# cistercianDisplay.net
KiCad netlist of a schematic drawn in EAGLE
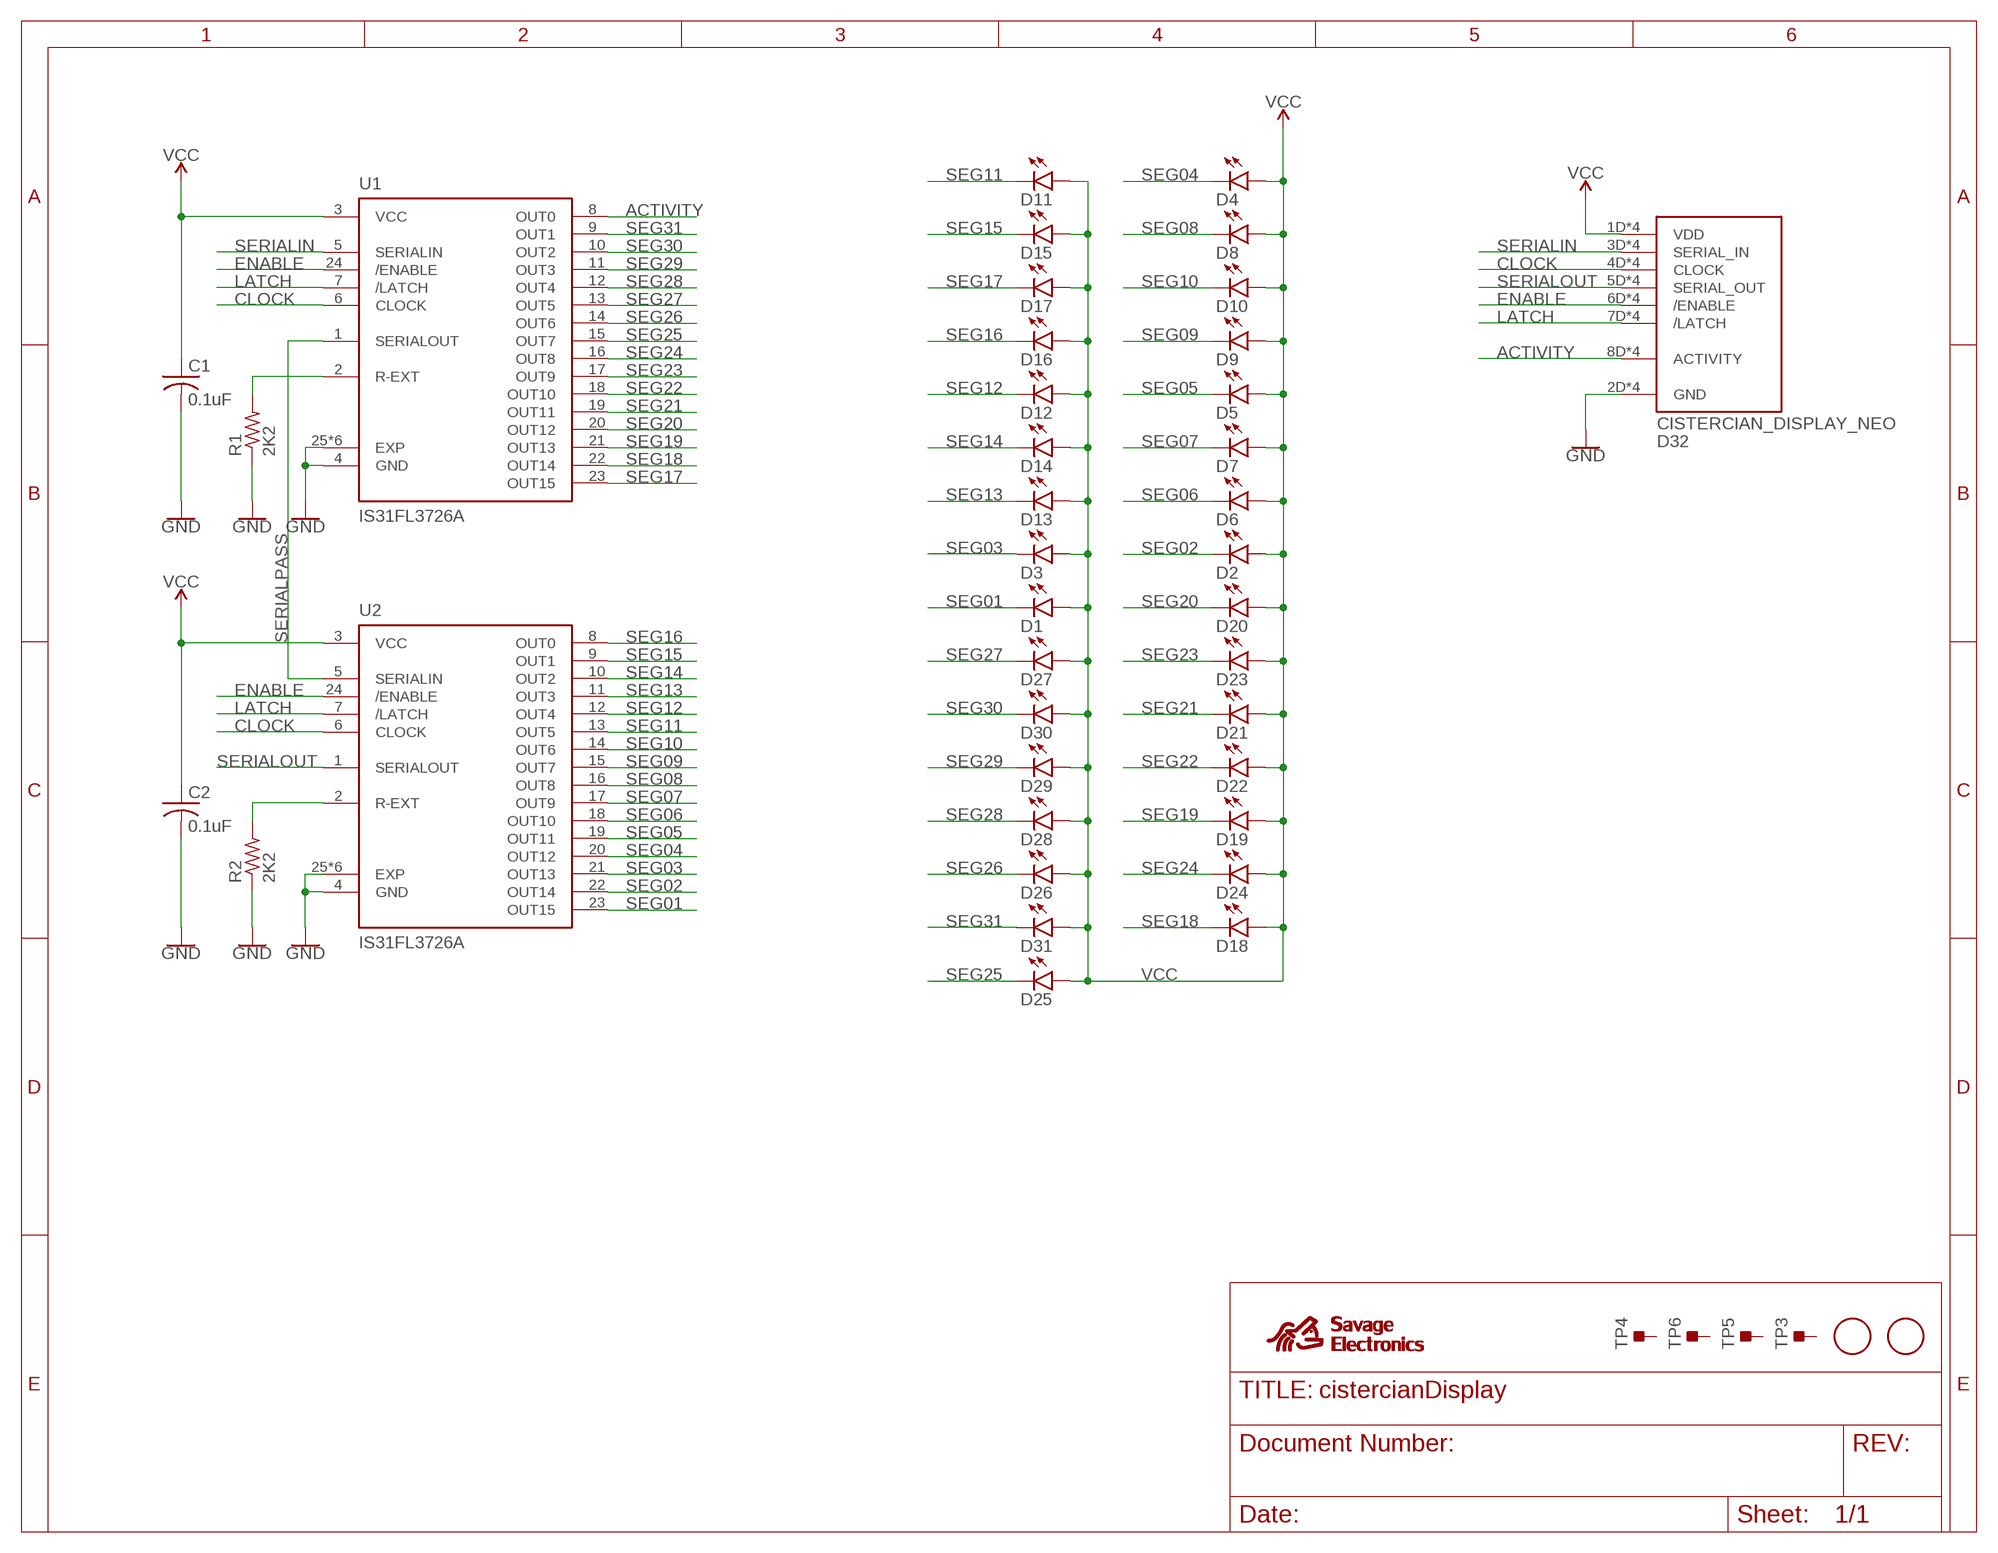
[diagram p0: schematic, sheet 1]

(export (version "E")
  (design (tool "Eeschema 10.0.6"))
  (components
    (comp (ref "C1")
      (value "0.1uF")
      (footprint "eagle-import:C0603")
      (libsource (lib "eagle-import") (part "C-USC0603"))
    )
    (comp (ref "C2")
      (value "0.1uF")
      (footprint "eagle-import:C0603")
      (libsource (lib "eagle-import") (part "C-USC0603"))
    )
    (comp (ref "D1")
      (value "LEDCHIP-LED0805")
      (footprint "eagle-import:CHIP-LED0805")
      (libsource (lib "eagle-import") (part "LEDCHIP-LED0805"))
    )
    (comp (ref "D2")
      (value "LEDCHIP-LED0805")
      (footprint "eagle-import:CHIP-LED0805")
      (libsource (lib "eagle-import") (part "LEDCHIP-LED0805"))
    )
    (comp (ref "D3")
      (value "LEDCHIP-LED0805")
      (footprint "eagle-import:CHIP-LED0805")
      (libsource (lib "eagle-import") (part "LEDCHIP-LED0805"))
    )
    (comp (ref "D4")
      (value "LEDCHIP-LED0805")
      (footprint "eagle-import:CHIP-LED0805")
      (libsource (lib "eagle-import") (part "LEDCHIP-LED0805"))
    )
    (comp (ref "D5")
      (value "LEDCHIP-LED0805")
      (footprint "eagle-import:CHIP-LED0805")
      (libsource (lib "eagle-import") (part "LEDCHIP-LED0805"))
    )
    (comp (ref "D6")
      (value "LEDCHIP-LED0805")
      (footprint "eagle-import:CHIP-LED0805")
      (libsource (lib "eagle-import") (part "LEDCHIP-LED0805"))
    )
    (comp (ref "D7")
      (value "LEDCHIP-LED0805")
      (footprint "eagle-import:CHIP-LED0805")
      (libsource (lib "eagle-import") (part "LEDCHIP-LED0805"))
    )
    (comp (ref "D8")
      (value "LEDCHIP-LED0805")
      (footprint "eagle-import:CHIP-LED0805")
      (libsource (lib "eagle-import") (part "LEDCHIP-LED0805"))
    )
    (comp (ref "D9")
      (value "LEDCHIP-LED0805")
      (footprint "eagle-import:CHIP-LED0805")
      (libsource (lib "eagle-import") (part "LEDCHIP-LED0805"))
    )
    (comp (ref "D10")
      (value "LEDCHIP-LED0805")
      (footprint "eagle-import:CHIP-LED0805")
      (libsource (lib "eagle-import") (part "LEDCHIP-LED0805"))
    )
    (comp (ref "D11")
      (value "LEDCHIP-LED0805")
      (footprint "eagle-import:CHIP-LED0805")
      (libsource (lib "eagle-import") (part "LEDCHIP-LED0805"))
    )
    (comp (ref "D12")
      (value "LEDCHIP-LED0805")
      (footprint "eagle-import:CHIP-LED0805")
      (libsource (lib "eagle-import") (part "LEDCHIP-LED0805"))
    )
    (comp (ref "D13")
      (value "LEDCHIP-LED0805")
      (footprint "eagle-import:CHIP-LED0805")
      (libsource (lib "eagle-import") (part "LEDCHIP-LED0805"))
    )
    (comp (ref "D14")
      (value "LEDCHIP-LED0805")
      (footprint "eagle-import:CHIP-LED0805")
      (libsource (lib "eagle-import") (part "LEDCHIP-LED0805"))
    )
    (comp (ref "D15")
      (value "LEDCHIP-LED0805")
      (footprint "eagle-import:CHIP-LED0805")
      (libsource (lib "eagle-import") (part "LEDCHIP-LED0805"))
    )
    (comp (ref "D16")
      (value "LEDCHIP-LED0805")
      (footprint "eagle-import:CHIP-LED0805")
      (libsource (lib "eagle-import") (part "LEDCHIP-LED0805"))
    )
    (comp (ref "D17")
      (value "LEDCHIP-LED0805")
      (footprint "eagle-import:CHIP-LED0805")
      (libsource (lib "eagle-import") (part "LEDCHIP-LED0805"))
    )
    (comp (ref "D18")
      (value "LEDCHIP-LED0805")
      (footprint "eagle-import:CHIP-LED0805")
      (libsource (lib "eagle-import") (part "LEDCHIP-LED0805"))
    )
    (comp (ref "D19")
      (value "LEDCHIP-LED0805")
      (footprint "eagle-import:CHIP-LED0805")
      (libsource (lib "eagle-import") (part "LEDCHIP-LED0805"))
    )
    (comp (ref "D20")
      (value "LEDCHIP-LED0805")
      (footprint "eagle-import:CHIP-LED0805")
      (libsource (lib "eagle-import") (part "LEDCHIP-LED0805"))
    )
    (comp (ref "D21")
      (value "LEDCHIP-LED0805")
      (footprint "eagle-import:CHIP-LED0805")
      (libsource (lib "eagle-import") (part "LEDCHIP-LED0805"))
    )
    (comp (ref "D22")
      (value "LEDCHIP-LED0805")
      (footprint "eagle-import:CHIP-LED0805")
      (libsource (lib "eagle-import") (part "LEDCHIP-LED0805"))
    )
    (comp (ref "D23")
      (value "LEDCHIP-LED0805")
      (footprint "eagle-import:CHIP-LED0805")
      (libsource (lib "eagle-import") (part "LEDCHIP-LED0805"))
    )
    (comp (ref "D24")
      (value "LEDCHIP-LED0805")
      (footprint "eagle-import:CHIP-LED0805")
      (libsource (lib "eagle-import") (part "LEDCHIP-LED0805"))
    )
    (comp (ref "D25")
      (value "LEDCHIP-LED0805")
      (footprint "eagle-import:CHIP-LED0805")
      (libsource (lib "eagle-import") (part "LEDCHIP-LED0805"))
    )
    (comp (ref "D26")
      (value "LEDCHIP-LED0805")
      (footprint "eagle-import:CHIP-LED0805")
      (libsource (lib "eagle-import") (part "LEDCHIP-LED0805"))
    )
    (comp (ref "D27")
      (value "LEDCHIP-LED0805")
      (footprint "eagle-import:CHIP-LED0805")
      (libsource (lib "eagle-import") (part "LEDCHIP-LED0805"))
    )
    (comp (ref "D28")
      (value "LEDCHIP-LED0805")
      (footprint "eagle-import:CHIP-LED0805")
      (libsource (lib "eagle-import") (part "LEDCHIP-LED0805"))
    )
    (comp (ref "D29")
      (value "LEDCHIP-LED0805")
      (footprint "eagle-import:CHIP-LED0805")
      (libsource (lib "eagle-import") (part "LEDCHIP-LED0805"))
    )
    (comp (ref "D30")
      (value "LEDCHIP-LED0805")
      (footprint "eagle-import:CHIP-LED0805")
      (libsource (lib "eagle-import") (part "LEDCHIP-LED0805"))
    )
    (comp (ref "D31")
      (value "LEDCHIP-LED0805")
      (footprint "eagle-import:CHIP-LED0805")
      (libsource (lib "eagle-import") (part "LEDCHIP-LED0805"))
    )
    (comp (ref "D32")
      (value "CISTERCIAN_DISPLAY_NEO")
      (footprint "eagle-import:CISTERCIAN_DISPLAYNEO")
      (libsource (lib "eagle-import") (part "CISTERCIAN_DISPLAY_NEO"))
    )
    (comp (ref "R1")
      (value "2K2")
      (footprint "eagle-import:R0603")
      (libsource (lib "eagle-import") (part "R-US_R0603"))
    )
    (comp (ref "R2")
      (value "2K2")
      (footprint "eagle-import:R0603")
      (libsource (lib "eagle-import") (part "R-US_R0603"))
    )
    (comp (ref "TP3")
      (value "TESTPOINT_TPS-SMD-10SN")
      (footprint "eagle-import:TESTPOINT_SMD-10SN")
      (libsource (lib "eagle-import") (part "TESTPOINT_TPS-SMD-10SN"))
    )
    (comp (ref "TP4")
      (value "TESTPOINT_TPS-SMD-10SN")
      (footprint "eagle-import:TESTPOINT_SMD-10SN")
      (libsource (lib "eagle-import") (part "TESTPOINT_TPS-SMD-10SN"))
    )
    (comp (ref "TP5")
      (value "TESTPOINT_TPS-SMD-10SN")
      (footprint "eagle-import:TESTPOINT_SMD-10SN")
      (libsource (lib "eagle-import") (part "TESTPOINT_TPS-SMD-10SN"))
    )
    (comp (ref "TP6")
      (value "TESTPOINT_TPS-SMD-10SN")
      (footprint "eagle-import:TESTPOINT_SMD-10SN")
      (libsource (lib "eagle-import") (part "TESTPOINT_TPS-SMD-10SN"))
    )
    (comp (ref "U$1")
      (value "FIDUCIAL")
      (footprint "eagle-import:FIDUCIAL_1MM")
      (libsource (lib "eagle-import") (part "FIDUCIAL"))
    )
    (comp (ref "U$2")
      (value "FIDUCIAL")
      (footprint "eagle-import:FIDUCIAL_1MM")
      (libsource (lib "eagle-import") (part "FIDUCIAL"))
    )
    (comp (ref "U$3")
      (value "SE_SMALL_STOP")
      (footprint "eagle-import:SE_SMALL_STOP")
      (libsource (lib "eagle-import") (part "SE_SMALL_STOP"))
    )
    (comp (ref "U1")
      (value "IS31FL3726A")
      (footprint "eagle-import:QFN50P400X400X90-25N")
      (fields (field (name "MF") "Microchip") (field (name "MP") "ATSAMD10D13A-MNT"))
      (libsource (lib "eagle-import") (part "IS31FL3726A"))
    )
    (comp (ref "U2")
      (value "IS31FL3726A")
      (footprint "eagle-import:QFN50P400X400X90-25N")
      (fields (field (name "MF") "Microchip") (field (name "MP") "ATSAMD10D13A-MNT"))
      (libsource (lib "eagle-import") (part "IS31FL3726A"))
    )
  )
  (nets
    (net (code "1") (name "/ACTIVITY") (class "Default")
      (node (ref "D32") (pin "8D") (pinfunction "ACTIVITY_8D") (pintype "bidirectional"))
      (node (ref "D32") (pin "8DC") (pinfunction "ACTIVITY_8DC") (pintype "bidirectional"))
      (node (ref "D32") (pin "8U") (pinfunction "ACTIVITY_8U") (pintype "bidirectional"))
      (node (ref "D32") (pin "8UC") (pinfunction "ACTIVITY_8UC") (pintype "bidirectional"))
      (node (ref "U1") (pin "8") (pinfunction "OUT0_8") (pintype "bidirectional"))
    )
    (net (code "2") (name "/CLOCK") (class "Default")
      (node (ref "D32") (pin "4D") (pinfunction "CLOCK_4D") (pintype "bidirectional"))
      (node (ref "D32") (pin "4DC") (pinfunction "CLOCK_4DC") (pintype "bidirectional"))
      (node (ref "D32") (pin "4U") (pinfunction "CLOCK_4U") (pintype "bidirectional"))
      (node (ref "D32") (pin "4UC") (pinfunction "CLOCK_4UC") (pintype "bidirectional"))
      (node (ref "U1") (pin "6") (pinfunction "CLOCK_6") (pintype "bidirectional"))
      (node (ref "U2") (pin "6") (pinfunction "CLOCK_6") (pintype "bidirectional"))
    )
    (net (code "3") (name "/ENABLE") (class "Default")
      (node (ref "D32") (pin "6D") (pinfunction "/ENABLE_6D") (pintype "bidirectional"))
      (node (ref "D32") (pin "6DC") (pinfunction "/ENABLE_6DC") (pintype "bidirectional"))
      (node (ref "D32") (pin "6U") (pinfunction "/ENABLE_6U") (pintype "bidirectional"))
      (node (ref "D32") (pin "6UC") (pinfunction "/ENABLE_6UC") (pintype "bidirectional"))
      (node (ref "U1") (pin "24") (pinfunction "/ENABLE_24") (pintype "bidirectional"))
      (node (ref "U2") (pin "24") (pinfunction "/ENABLE_24") (pintype "bidirectional"))
    )
    (net (code "4") (name "/LATCH") (class "Default")
      (node (ref "D32") (pin "7D") (pinfunction "/LATCH_7D") (pintype "bidirectional"))
      (node (ref "D32") (pin "7DC") (pinfunction "/LATCH_7DC") (pintype "bidirectional"))
      (node (ref "D32") (pin "7U") (pinfunction "/LATCH_7U") (pintype "bidirectional"))
      (node (ref "D32") (pin "7UC") (pinfunction "/LATCH_7UC") (pintype "bidirectional"))
      (node (ref "U1") (pin "7") (pinfunction "/LATCH_7") (pintype "bidirectional"))
      (node (ref "U2") (pin "7") (pinfunction "/LATCH_7") (pintype "bidirectional"))
    )
    (net (code "5") (name "/SEG01") (class "Default")
      (node (ref "D1") (pin "C") (pinfunction "C_C") (pintype "passive"))
      (node (ref "U2") (pin "23") (pinfunction "OUT15_23") (pintype "bidirectional"))
    )
    (net (code "6") (name "/SEG02") (class "Default")
      (node (ref "D2") (pin "C") (pinfunction "C_C") (pintype "passive"))
      (node (ref "U2") (pin "22") (pinfunction "OUT14_22") (pintype "bidirectional"))
    )
    (net (code "7") (name "/SEG03") (class "Default")
      (node (ref "D3") (pin "C") (pinfunction "C_C") (pintype "passive"))
      (node (ref "U2") (pin "21") (pinfunction "OUT13_21") (pintype "bidirectional"))
    )
    (net (code "8") (name "/SEG04") (class "Default")
      (node (ref "D4") (pin "C") (pinfunction "C_C") (pintype "passive"))
      (node (ref "U2") (pin "20") (pinfunction "OUT12_20") (pintype "bidirectional"))
    )
    (net (code "9") (name "/SEG05") (class "Default")
      (node (ref "D5") (pin "C") (pinfunction "C_C") (pintype "passive"))
      (node (ref "U2") (pin "19") (pinfunction "OUT11_19") (pintype "bidirectional"))
    )
    (net (code "10") (name "/SEG06") (class "Default")
      (node (ref "D6") (pin "C") (pinfunction "C_C") (pintype "passive"))
      (node (ref "U2") (pin "18") (pinfunction "OUT10_18") (pintype "bidirectional"))
    )
    (net (code "11") (name "/SEG07") (class "Default")
      (node (ref "D7") (pin "C") (pinfunction "C_C") (pintype "passive"))
      (node (ref "U2") (pin "17") (pinfunction "OUT9_17") (pintype "bidirectional"))
    )
    (net (code "12") (name "/SEG08") (class "Default")
      (node (ref "D8") (pin "C") (pinfunction "C_C") (pintype "passive"))
      (node (ref "U2") (pin "16") (pinfunction "OUT8_16") (pintype "bidirectional"))
    )
    (net (code "13") (name "/SEG09") (class "Default")
      (node (ref "D9") (pin "C") (pinfunction "C_C") (pintype "passive"))
      (node (ref "U2") (pin "15") (pinfunction "OUT7_15") (pintype "bidirectional"))
    )
    (net (code "14") (name "/SEG10") (class "Default")
      (node (ref "D10") (pin "C") (pinfunction "C_C") (pintype "passive"))
      (node (ref "U2") (pin "14") (pinfunction "OUT6_14") (pintype "bidirectional"))
    )
    (net (code "15") (name "/SEG11") (class "Default")
      (node (ref "D11") (pin "C") (pinfunction "C_C") (pintype "passive"))
      (node (ref "U2") (pin "13") (pinfunction "OUT5_13") (pintype "bidirectional"))
    )
    (net (code "16") (name "/SEG12") (class "Default")
      (node (ref "D12") (pin "C") (pinfunction "C_C") (pintype "passive"))
      (node (ref "U2") (pin "12") (pinfunction "OUT4_12") (pintype "bidirectional"))
    )
    (net (code "17") (name "/SEG13") (class "Default")
      (node (ref "D13") (pin "C") (pinfunction "C_C") (pintype "passive"))
      (node (ref "U2") (pin "11") (pinfunction "OUT3_11") (pintype "bidirectional"))
    )
    (net (code "18") (name "/SEG14") (class "Default")
      (node (ref "D14") (pin "C") (pinfunction "C_C") (pintype "passive"))
      (node (ref "U2") (pin "10") (pinfunction "OUT2_10") (pintype "bidirectional"))
    )
    (net (code "19") (name "/SEG15") (class "Default")
      (node (ref "D15") (pin "C") (pinfunction "C_C") (pintype "passive"))
      (node (ref "U2") (pin "9") (pinfunction "OUT1_9") (pintype "bidirectional"))
    )
    (net (code "20") (name "/SEG16") (class "Default")
      (node (ref "D16") (pin "C") (pinfunction "C_C") (pintype "passive"))
      (node (ref "U2") (pin "8") (pinfunction "OUT0_8") (pintype "bidirectional"))
    )
    (net (code "21") (name "/SEG17") (class "Default")
      (node (ref "D17") (pin "C") (pinfunction "C_C") (pintype "passive"))
      (node (ref "U1") (pin "23") (pinfunction "OUT15_23") (pintype "bidirectional"))
    )
    (net (code "22") (name "/SEG18") (class "Default")
      (node (ref "D18") (pin "C") (pinfunction "C_C") (pintype "passive"))
      (node (ref "U1") (pin "22") (pinfunction "OUT14_22") (pintype "bidirectional"))
    )
    (net (code "23") (name "/SEG19") (class "Default")
      (node (ref "D19") (pin "C") (pinfunction "C_C") (pintype "passive"))
      (node (ref "U1") (pin "21") (pinfunction "OUT13_21") (pintype "bidirectional"))
    )
    (net (code "24") (name "/SEG20") (class "Default")
      (node (ref "D20") (pin "C") (pinfunction "C_C") (pintype "passive"))
      (node (ref "U1") (pin "20") (pinfunction "OUT12_20") (pintype "bidirectional"))
    )
    (net (code "25") (name "/SEG21") (class "Default")
      (node (ref "D21") (pin "C") (pinfunction "C_C") (pintype "passive"))
      (node (ref "U1") (pin "19") (pinfunction "OUT11_19") (pintype "bidirectional"))
    )
    (net (code "26") (name "/SEG22") (class "Default")
      (node (ref "D22") (pin "C") (pinfunction "C_C") (pintype "passive"))
      (node (ref "U1") (pin "18") (pinfunction "OUT10_18") (pintype "bidirectional"))
    )
    (net (code "27") (name "/SEG23") (class "Default")
      (node (ref "D23") (pin "C") (pinfunction "C_C") (pintype "passive"))
      (node (ref "U1") (pin "17") (pinfunction "OUT9_17") (pintype "bidirectional"))
    )
    (net (code "28") (name "/SEG24") (class "Default")
      (node (ref "D24") (pin "C") (pinfunction "C_C") (pintype "passive"))
      (node (ref "U1") (pin "16") (pinfunction "OUT8_16") (pintype "bidirectional"))
    )
    (net (code "29") (name "/SEG25") (class "Default")
      (node (ref "D25") (pin "C") (pinfunction "C_C") (pintype "passive"))
      (node (ref "U1") (pin "15") (pinfunction "OUT7_15") (pintype "bidirectional"))
    )
    (net (code "30") (name "/SEG26") (class "Default")
      (node (ref "D26") (pin "C") (pinfunction "C_C") (pintype "passive"))
      (node (ref "U1") (pin "14") (pinfunction "OUT6_14") (pintype "bidirectional"))
    )
    (net (code "31") (name "/SEG27") (class "Default")
      (node (ref "D27") (pin "C") (pinfunction "C_C") (pintype "passive"))
      (node (ref "U1") (pin "13") (pinfunction "OUT5_13") (pintype "bidirectional"))
    )
    (net (code "32") (name "/SEG28") (class "Default")
      (node (ref "D28") (pin "C") (pinfunction "C_C") (pintype "passive"))
      (node (ref "U1") (pin "12") (pinfunction "OUT4_12") (pintype "bidirectional"))
    )
    (net (code "33") (name "/SEG29") (class "Default")
      (node (ref "D29") (pin "C") (pinfunction "C_C") (pintype "passive"))
      (node (ref "U1") (pin "11") (pinfunction "OUT3_11") (pintype "bidirectional"))
    )
    (net (code "34") (name "/SEG30") (class "Default")
      (node (ref "D30") (pin "C") (pinfunction "C_C") (pintype "passive"))
      (node (ref "U1") (pin "10") (pinfunction "OUT2_10") (pintype "bidirectional"))
    )
    (net (code "35") (name "/SEG31") (class "Default")
      (node (ref "D31") (pin "C") (pinfunction "C_C") (pintype "passive"))
      (node (ref "U1") (pin "9") (pinfunction "OUT1_9") (pintype "bidirectional"))
    )
    (net (code "36") (name "/SERIALIN") (class "Default")
      (node (ref "D32") (pin "3D") (pinfunction "SERIAL_IN_3D") (pintype "bidirectional"))
      (node (ref "D32") (pin "3DC") (pinfunction "SERIAL_IN_3DC") (pintype "bidirectional"))
      (node (ref "D32") (pin "3U") (pinfunction "SERIAL_IN_3U") (pintype "bidirectional"))
      (node (ref "D32") (pin "3UC") (pinfunction "SERIAL_IN_3UC") (pintype "bidirectional"))
      (node (ref "U1") (pin "5") (pinfunction "SERIALIN_5") (pintype "bidirectional"))
    )
    (net (code "37") (name "/SERIALOUT") (class "Default")
      (node (ref "D32") (pin "5D") (pinfunction "SERIAL_OUT_5D") (pintype "bidirectional"))
      (node (ref "D32") (pin "5DC") (pinfunction "SERIAL_OUT_5DC") (pintype "bidirectional"))
      (node (ref "D32") (pin "5U") (pinfunction "SERIAL_OUT_5U") (pintype "bidirectional"))
      (node (ref "D32") (pin "5UC") (pinfunction "SERIAL_OUT_5UC") (pintype "bidirectional"))
      (node (ref "U2") (pin "1") (pinfunction "SERIALOUT_1") (pintype "bidirectional"))
    )
    (net (code "38") (name "/SERIALPASS") (class "Default")
      (node (ref "U1") (pin "1") (pinfunction "SERIALOUT_1") (pintype "bidirectional"))
      (node (ref "U2") (pin "5") (pinfunction "SERIALIN_5") (pintype "bidirectional"))
    )
    (net (code "39") (name "GND") (class "Default")
      (node (ref "C1") (pin "2") (pinfunction "2_2") (pintype "passive"))
      (node (ref "C2") (pin "2") (pinfunction "2_2") (pintype "passive"))
      (node (ref "D32") (pin "2D") (pinfunction "GND_2D") (pintype "bidirectional"))
      (node (ref "D32") (pin "2DC") (pinfunction "GND_2DC") (pintype "bidirectional"))
      (node (ref "D32") (pin "2U") (pinfunction "GND_2U") (pintype "bidirectional"))
      (node (ref "D32") (pin "2UC") (pinfunction "GND_2UC") (pintype "bidirectional"))
      (node (ref "R1") (pin "1") (pinfunction "1_1") (pintype "passive"))
      (node (ref "R2") (pin "1") (pinfunction "1_1") (pintype "passive"))
      (node (ref "U1") (pin "25") (pinfunction "EXP_25") (pintype "passive"))
      (node (ref "U1") (pin "4") (pinfunction "GND_4") (pintype "power_in"))
      (node (ref "U1") (pin "P$1") (pinfunction "EXP_P$1") (pintype "passive"))
      (node (ref "U1") (pin "P$2") (pinfunction "EXP_P$2") (pintype "passive"))
      (node (ref "U1") (pin "P$3") (pinfunction "EXP_P$3") (pintype "passive"))
      (node (ref "U1") (pin "P$4") (pinfunction "EXP_P$4") (pintype "passive"))
      (node (ref "U1") (pin "P$5") (pinfunction "EXP_P$5") (pintype "passive"))
      (node (ref "U2") (pin "25") (pinfunction "EXP_25") (pintype "passive"))
      (node (ref "U2") (pin "4") (pinfunction "GND_4") (pintype "power_in"))
      (node (ref "U2") (pin "P$1") (pinfunction "EXP_P$1") (pintype "passive"))
      (node (ref "U2") (pin "P$2") (pinfunction "EXP_P$2") (pintype "passive"))
      (node (ref "U2") (pin "P$3") (pinfunction "EXP_P$3") (pintype "passive"))
      (node (ref "U2") (pin "P$4") (pinfunction "EXP_P$4") (pintype "passive"))
      (node (ref "U2") (pin "P$5") (pinfunction "EXP_P$5") (pintype "passive"))
    )
    (net (code "40") (name "Net-(U1-R-EXT)") (class "Default")
      (node (ref "R1") (pin "2") (pinfunction "2_2") (pintype "passive"))
      (node (ref "U1") (pin "2") (pinfunction "R-EXT_2") (pintype "bidirectional"))
    )
    (net (code "41") (name "Net-(U2-R-EXT)") (class "Default")
      (node (ref "R2") (pin "2") (pinfunction "2_2") (pintype "passive"))
      (node (ref "U2") (pin "2") (pinfunction "R-EXT_2") (pintype "bidirectional"))
    )
    (net (code "42") (name "VCC") (class "Default")
      (node (ref "C1") (pin "1") (pinfunction "1_1") (pintype "passive"))
      (node (ref "C2") (pin "1") (pinfunction "1_1") (pintype "passive"))
      (node (ref "D1") (pin "A") (pinfunction "A_A") (pintype "passive"))
      (node (ref "D10") (pin "A") (pinfunction "A_A") (pintype "passive"))
      (node (ref "D11") (pin "A") (pinfunction "A_A") (pintype "passive"))
      (node (ref "D12") (pin "A") (pinfunction "A_A") (pintype "passive"))
      (node (ref "D13") (pin "A") (pinfunction "A_A") (pintype "passive"))
      (node (ref "D14") (pin "A") (pinfunction "A_A") (pintype "passive"))
      (node (ref "D15") (pin "A") (pinfunction "A_A") (pintype "passive"))
      (node (ref "D16") (pin "A") (pinfunction "A_A") (pintype "passive"))
      (node (ref "D17") (pin "A") (pinfunction "A_A") (pintype "passive"))
      (node (ref "D18") (pin "A") (pinfunction "A_A") (pintype "passive"))
      (node (ref "D19") (pin "A") (pinfunction "A_A") (pintype "passive"))
      (node (ref "D2") (pin "A") (pinfunction "A_A") (pintype "passive"))
      (node (ref "D20") (pin "A") (pinfunction "A_A") (pintype "passive"))
      (node (ref "D21") (pin "A") (pinfunction "A_A") (pintype "passive"))
      (node (ref "D22") (pin "A") (pinfunction "A_A") (pintype "passive"))
      (node (ref "D23") (pin "A") (pinfunction "A_A") (pintype "passive"))
      (node (ref "D24") (pin "A") (pinfunction "A_A") (pintype "passive"))
      (node (ref "D25") (pin "A") (pinfunction "A_A") (pintype "passive"))
      (node (ref "D26") (pin "A") (pinfunction "A_A") (pintype "passive"))
      (node (ref "D27") (pin "A") (pinfunction "A_A") (pintype "passive"))
      (node (ref "D28") (pin "A") (pinfunction "A_A") (pintype "passive"))
      (node (ref "D29") (pin "A") (pinfunction "A_A") (pintype "passive"))
      (node (ref "D3") (pin "A") (pinfunction "A_A") (pintype "passive"))
      (node (ref "D30") (pin "A") (pinfunction "A_A") (pintype "passive"))
      (node (ref "D31") (pin "A") (pinfunction "A_A") (pintype "passive"))
      (node (ref "D32") (pin "1D") (pinfunction "VDD_1D") (pintype "bidirectional"))
      (node (ref "D32") (pin "1DC") (pinfunction "VDD_1DC") (pintype "bidirectional"))
      (node (ref "D32") (pin "1U") (pinfunction "VDD_1U") (pintype "bidirectional"))
      (node (ref "D32") (pin "1UC") (pinfunction "VDD_1UC") (pintype "bidirectional"))
      (node (ref "D4") (pin "A") (pinfunction "A_A") (pintype "passive"))
      (node (ref "D5") (pin "A") (pinfunction "A_A") (pintype "passive"))
      (node (ref "D6") (pin "A") (pinfunction "A_A") (pintype "passive"))
      (node (ref "D7") (pin "A") (pinfunction "A_A") (pintype "passive"))
      (node (ref "D8") (pin "A") (pinfunction "A_A") (pintype "passive"))
      (node (ref "D9") (pin "A") (pinfunction "A_A") (pintype "passive"))
      (node (ref "U1") (pin "3") (pinfunction "VCC_3") (pintype "power_in"))
      (node (ref "U2") (pin "3") (pinfunction "VCC_3") (pintype "power_in"))
    )
    (net (code "43") (name "unconnected-(TP3-PadTP)") (class "Default")
      (node (ref "TP3") (pin "TP") (pinfunction "TP_TP") (pintype "passive"))
    )
    (net (code "44") (name "unconnected-(TP4-PadTP)") (class "Default")
      (node (ref "TP4") (pin "TP") (pinfunction "TP_TP") (pintype "passive"))
    )
    (net (code "45") (name "unconnected-(TP5-PadTP)") (class "Default")
      (node (ref "TP5") (pin "TP") (pinfunction "TP_TP") (pintype "passive"))
    )
    (net (code "46") (name "unconnected-(TP6-PadTP)") (class "Default")
      (node (ref "TP6") (pin "TP") (pinfunction "TP_TP") (pintype "passive"))
    )
  )
)
